# MDL_CONTROL.net
KiCad netlist of a schematic drawn in Altium Designer
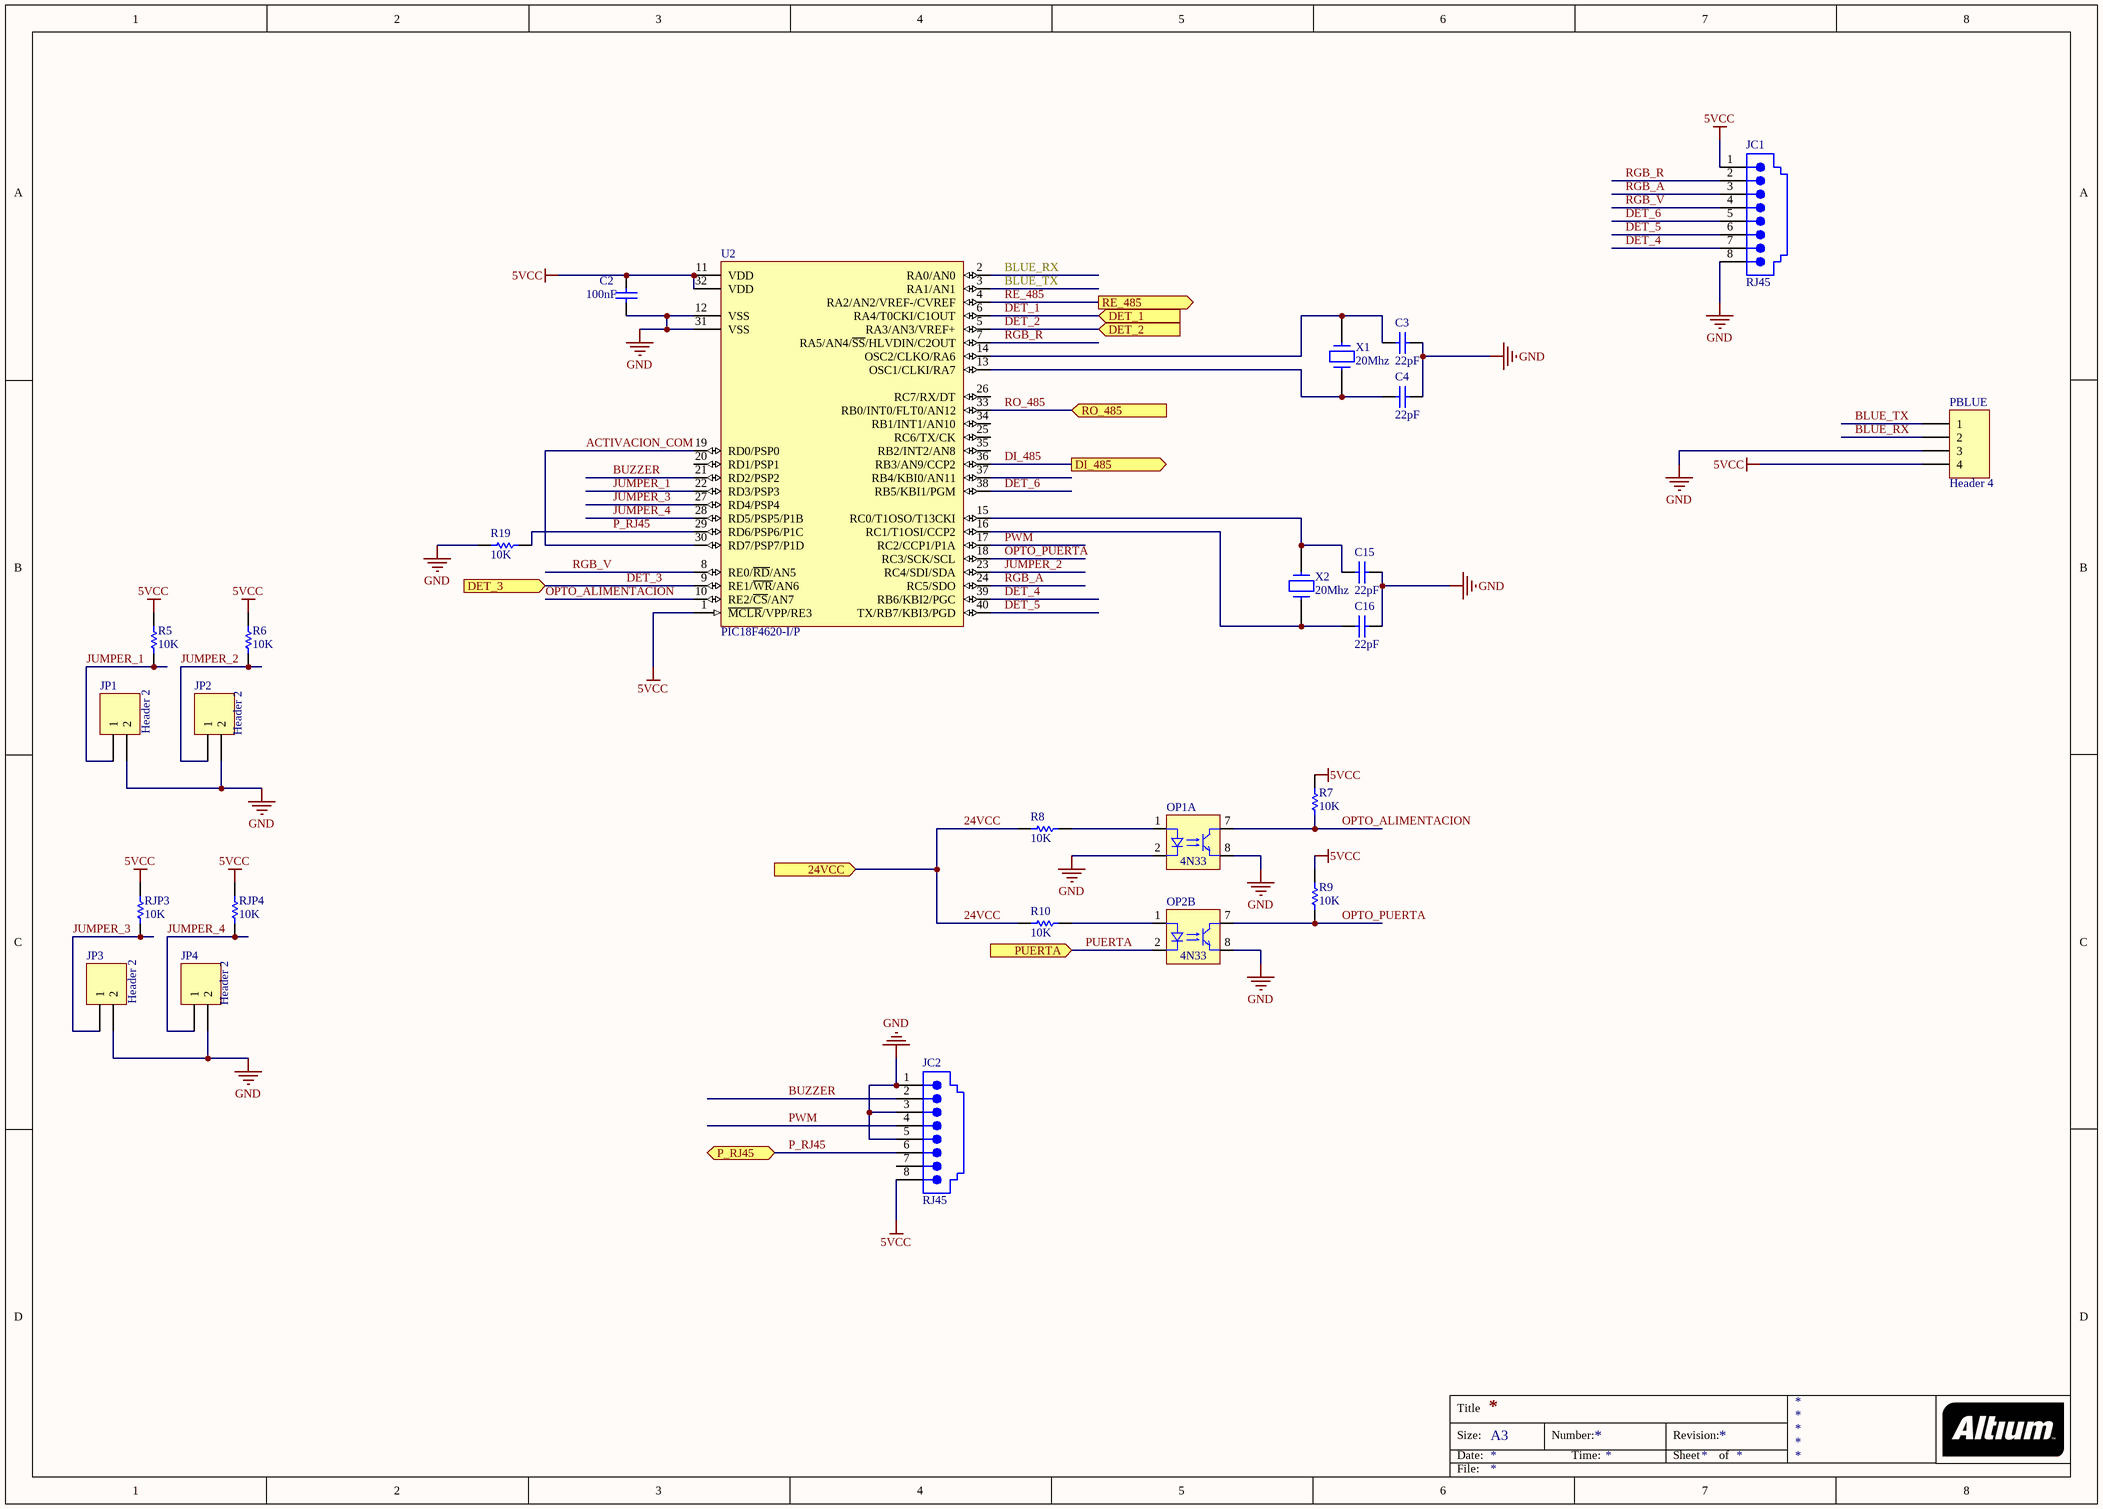
[diagram p0: MDL_CONTROL.SchDoc]

(export (version "E")
  (design (tool "Eeschema 10.0.6"))
  (components
    (comp (ref "C2")
      (value "100nF")
      (footprint "VP44-2.5")
      (description "Dipped Radial Multilayer Ceramic Capacitor X7R: 220nF, 100V")
      (fields (field (name "Comment") "VP44BY224JB") (field (name "PUBLISHER") "Altium Limited"))
      (libsource (lib "Vishay Vitramon Ceramic Dipped Capacitor") (part "VP44BY224JB"))
    )
    (comp (ref "C3")
      (value "22pF")
      (footprint "VP31-2.5")
      (description "Dipped Radial Multilayer Ceramic Capacitor COG (NPO): 22pF, 100V")
      (fields (field (name "Comment") "VP31BA220JB") (field (name "PUBLISHER") "Altium Limited"))
      (libsource (lib "Vishay Vitramon Ceramic Dipped Capacitor") (part "VP31BA220JB"))
    )
    (comp (ref "C4")
      (value "22pF")
      (footprint "VP31-2.5")
      (description "Dipped Radial Multilayer Ceramic Capacitor COG (NPO): 22pF, 100V")
      (fields (field (name "Comment") "VP31BA220JB") (field (name "PUBLISHER") "Altium Limited"))
      (libsource (lib "Vishay Vitramon Ceramic Dipped Capacitor") (part "VP31BA220JB"))
    )
    (comp (ref "C15")
      (value "22pF")
      (footprint "VP31-2.5")
      (description "Dipped Radial Multilayer Ceramic Capacitor COG (NPO): 22pF, 100V")
      (fields (field (name "Comment") "VP31BA220JB") (field (name "PUBLISHER") "Altium Limited"))
      (libsource (lib "Vishay Vitramon Ceramic Dipped Capacitor") (part "VP31BA220JB"))
    )
    (comp (ref "C16")
      (value "22pF")
      (footprint "VP31-2.5")
      (description "Dipped Radial Multilayer Ceramic Capacitor COG (NPO): 22pF, 100V")
      (fields (field (name "Comment") "VP31BA220JB") (field (name "PUBLISHER") "Altium Limited"))
      (libsource (lib "Vishay Vitramon Ceramic Dipped Capacitor") (part "VP31BA220JB"))
    )
    (comp (ref "JC1")
      (value "RJ45")
      (footprint "15-43-6233")
      (description "Right Angle, Standard Profile, RJ45-Keyed, Flange Mount PCB Jack")
      (fields (field (name "PUBLISHER") "Altium Limited"))
      (libsource (lib "Molex Modular Jack Right Angle") (part "15-43-6233"))
    )
    (comp (ref "JC2")
      (value "RJ45")
      (footprint "15-43-6233")
      (description "Right Angle, Standard Profile, RJ45-Keyed, Flange Mount PCB Jack")
      (fields (field (name "PUBLISHER") "Altium Limited"))
      (libsource (lib "Molex Modular Jack Right Angle") (part "15-43-6233"))
    )
    (comp (ref "JP1")
      (value "Header 2")
      (footprint "HDR1X2")
      (description "Header, 2-Pin")
      (fields (field (name "PUBLISHER") "Altium Limited"))
      (libsource (lib "Miscellaneous Connectors") (part "Header 2"))
    )
    (comp (ref "JP2")
      (value "Header 2")
      (footprint "HDR1X2")
      (description "Header, 2-Pin")
      (fields (field (name "PUBLISHER") "Altium Limited"))
      (libsource (lib "Miscellaneous Connectors") (part "Header 2"))
    )
    (comp (ref "JP3")
      (value "Header 2")
      (footprint "HDR1X2")
      (description "Header, 2-Pin")
      (fields (field (name "PUBLISHER") "Altium Limited"))
      (libsource (lib "Miscellaneous Connectors") (part "Header 2"))
    )
    (comp (ref "JP4")
      (value "Header 2")
      (footprint "HDR1X2")
      (description "Header, 2-Pin")
      (fields (field (name "PUBLISHER") "Altium Limited"))
      (libsource (lib "Miscellaneous Connectors") (part "Header 2"))
    )
    (comp (ref "OP1")
      (value "4N33")
      (footprint "4n35_4n33_6pines")
      (description "Optocoupler, Phototransistor Output, Dual Channel, TTL Compatible, Pb-free")
      (fields (field (name "PUBLISHER") "Altium Limited"))
      (libsource (lib "Vishay Optoelectronic Optocoupler") (part "ILD74"))
    )
    (comp (ref "OP2")
      (value "4N33")
      (footprint "4n35_4n33_6pines")
      (description "Optocoupler, Phototransistor Output, Dual Channel, TTL Compatible, Pb-free")
      (fields (field (name "PUBLISHER") "Altium Limited"))
      (libsource (lib "") (part "ILD74_1"))
    )
    (comp (ref "PBLUE")
      (value "Header 4")
      (footprint "HDR1X4")
      (description "Header, 4-Pin")
      (fields (field (name "PUBLISHER") "Altium Limited"))
      (libsource (lib "Miscellaneous Connectors") (part "Header 4"))
    )
    (comp (ref "R5")
      (value "10K")
      (footprint "AXIAL-0.3")
      (description "Resistor")
      (fields (field (name "Comment") "Res") (field (name "PUBLISHER") "Altium Limited"))
      (libsource (lib "Miscellaneous Devices") (part "Res1"))
    )
    (comp (ref "R6")
      (value "10K")
      (footprint "AXIAL-0.3")
      (description "Resistor")
      (fields (field (name "Comment") "Res") (field (name "PUBLISHER") "Altium Limited"))
      (libsource (lib "Miscellaneous Devices") (part "Res1"))
    )
    (comp (ref "R7")
      (value "10K")
      (footprint "AXIAL-0.3")
      (description "Resistor")
      (fields (field (name "Comment") "Res") (field (name "PUBLISHER") "Altium Limited"))
      (libsource (lib "Miscellaneous Devices") (part "Res1"))
    )
    (comp (ref "R8")
      (value "10K")
      (footprint "AXIAL-0.3")
      (description "Resistor")
      (fields (field (name "Comment") "Res") (field (name "PUBLISHER") "Altium Limited"))
      (libsource (lib "Miscellaneous Devices") (part "Res1"))
    )
    (comp (ref "R9")
      (value "10K")
      (footprint "AXIAL-0.3")
      (description "Resistor")
      (fields (field (name "Comment") "Res") (field (name "PUBLISHER") "Altium Limited"))
      (libsource (lib "Miscellaneous Devices") (part "Res1"))
    )
    (comp (ref "R10")
      (value "10K")
      (footprint "AXIAL-0.3")
      (description "Resistor")
      (fields (field (name "Comment") "Res") (field (name "PUBLISHER") "Altium Limited"))
      (libsource (lib "Miscellaneous Devices") (part "Res1"))
    )
    (comp (ref "R19")
      (value "10K")
      (footprint "AXIAL-0.3")
      (description "Resistor")
      (fields (field (name "Comment") "Res") (field (name "PUBLISHER") "Altium Limited"))
      (libsource (lib "Miscellaneous Devices") (part "Res1"))
    )
    (comp (ref "RJP3")
      (value "10K")
      (footprint "AXIAL-0.3")
      (description "Resistor")
      (fields (field (name "Comment") "Res") (field (name "PUBLISHER") "Altium Limited"))
      (libsource (lib "Miscellaneous Devices") (part "Res1"))
    )
    (comp (ref "RJP4")
      (value "10K")
      (footprint "AXIAL-0.3")
      (description "Resistor")
      (fields (field (name "Comment") "Res") (field (name "PUBLISHER") "Altium Limited"))
      (libsource (lib "Miscellaneous Devices") (part "Res1"))
    )
    (comp (ref "U2")
      (value "PIC18F4620-I/P")
      (footprint "PDIP600-P40")
      (fields (field (name "PUBLISHER") "Altium Limited"))
      (libsource (lib "Microchip Microcontroller 8-Bit PIC18") (part "PIC18F4620-I/P"))
    )
    (comp (ref "X1")
      (value "20Mhz")
      (footprint "XTAL-1")
      (description "Cristal de cuarzo")
      (fields (field (name "X1") "20Mhz"))
      (libsource (lib "Cristales de cuarzo") (part "Cristal de cuarzo"))
    )
    (comp (ref "X2")
      (value "20Mhz")
      (footprint "XTAL-1")
      (description "Cristal de cuarzo")
      (fields (field (name "X1") "20Mhz"))
      (libsource (lib "Cristales de cuarzo") (part "Cristal de cuarzo"))
    )
  )
  (nets
    (net (code "1") (name "/24VCC") (class "Default")
      (node (ref "R10") (pin "1") (pinfunction "1_1") (pintype "passive"))
      (node (ref "R8") (pin "1") (pinfunction "1_1") (pintype "passive"))
    )
    (net (code "2") (name "/ACTIVACION_COM") (class "Default")
      (node (ref "U2") (pin "19") (pinfunction "RD0/PSP0_19") (pintype "bidirectional"))
      (node (ref "U2") (pin "30") (pinfunction "RD7/PSP7/P1D_30") (pintype "bidirectional"))
    )
    (net (code "3") (name "/BLUE_RX") (class "Default")
      (node (ref "PBLUE") (pin "2") (pinfunction "2_2") (pintype "passive"))
      (node (ref "U2") (pin "2") (pinfunction "RA0/AN0_2") (pintype "bidirectional"))
    )
    (net (code "4") (name "/BLUE_TX") (class "Default")
      (node (ref "PBLUE") (pin "1") (pinfunction "1_1") (pintype "passive"))
      (node (ref "U2") (pin "3") (pinfunction "RA1/AN1_3") (pintype "bidirectional"))
    )
    (net (code "5") (name "/BUZZER") (class "Default")
      (node (ref "JC2") (pin "2") (pinfunction "2_2") (pintype "passive"))
      (node (ref "U2") (pin "21") (pinfunction "RD2/PSP2_21") (pintype "bidirectional"))
    )
    (net (code "6") (name "/DET_1") (class "Default")
      (node (ref "U2") (pin "6") (pinfunction "RA4/T0CKI/C1OUT_6") (pintype "bidirectional"))
    )
    (net (code "7") (name "/DET_2") (class "Default")
      (node (ref "U2") (pin "5") (pinfunction "RA3/AN3/VREF+_5") (pintype "bidirectional"))
    )
    (net (code "8") (name "/DET_3") (class "Default")
      (node (ref "U2") (pin "9") (pinfunction "RE1/~{WR}/AN6_9") (pintype "bidirectional"))
    )
    (net (code "9") (name "/DET_4") (class "Default")
      (node (ref "JC1") (pin "7") (pinfunction "7_7") (pintype "passive"))
      (node (ref "U2") (pin "39") (pinfunction "RB6/KBI2/PGC_39") (pintype "bidirectional"))
    )
    (net (code "10") (name "/DET_5") (class "Default")
      (node (ref "JC1") (pin "6") (pinfunction "6_6") (pintype "passive"))
      (node (ref "U2") (pin "40") (pinfunction "TX/RB7/KBI3/PGD_40") (pintype "bidirectional"))
    )
    (net (code "11") (name "/DET_6") (class "Default")
      (node (ref "JC1") (pin "5") (pinfunction "5_5") (pintype "passive"))
      (node (ref "U2") (pin "38") (pinfunction "RB5/KBI1/PGM_38") (pintype "bidirectional"))
    )
    (net (code "12") (name "/DI_485") (class "Default")
      (node (ref "U2") (pin "36") (pinfunction "RB3/AN9/CCP2_36") (pintype "bidirectional"))
    )
    (net (code "13") (name "/JUMPER_1") (class "Default")
      (node (ref "JP1") (pin "1") (pinfunction "1_1") (pintype "passive"))
      (node (ref "R5") (pin "1") (pinfunction "1_1") (pintype "passive"))
      (node (ref "U2") (pin "22") (pinfunction "RD3/PSP3_22") (pintype "bidirectional"))
    )
    (net (code "14") (name "/JUMPER_2") (class "Default")
      (node (ref "JP2") (pin "1") (pinfunction "1_1") (pintype "passive"))
      (node (ref "R6") (pin "1") (pinfunction "1_1") (pintype "passive"))
      (node (ref "U2") (pin "23") (pinfunction "RC4/SDI/SDA_23") (pintype "bidirectional"))
    )
    (net (code "15") (name "/JUMPER_3") (class "Default")
      (node (ref "JP3") (pin "1") (pinfunction "1_1") (pintype "passive"))
      (node (ref "RJP3") (pin "1") (pinfunction "1_1") (pintype "passive"))
      (node (ref "U2") (pin "27") (pinfunction "RD4/PSP4_27") (pintype "bidirectional"))
    )
    (net (code "16") (name "/JUMPER_4") (class "Default")
      (node (ref "JP4") (pin "1") (pinfunction "1_1") (pintype "passive"))
      (node (ref "RJP4") (pin "1") (pinfunction "1_1") (pintype "passive"))
      (node (ref "U2") (pin "28") (pinfunction "RD5/PSP5/P1B_28") (pintype "bidirectional"))
    )
    (net (code "17") (name "/OPTO_ALIMENTACION") (class "Default")
      (node (ref "OP1") (pin "7") (pinfunction "C_7") (pintype "passive"))
      (node (ref "R7") (pin "1") (pinfunction "1_1") (pintype "passive"))
      (node (ref "U2") (pin "10") (pinfunction "RE2/~{CS}/AN7_10") (pintype "bidirectional"))
    )
    (net (code "18") (name "/OPTO_PUERTA") (class "Default")
      (node (ref "OP2") (pin "7") (pinfunction "C_7") (pintype "passive"))
      (node (ref "R9") (pin "1") (pinfunction "1_1") (pintype "passive"))
      (node (ref "U2") (pin "18") (pinfunction "RC3/SCK/SCL_18") (pintype "bidirectional"))
    )
    (net (code "19") (name "/PUERTA") (class "Default")
      (node (ref "OP2") (pin "2") (pinfunction "K_2") (pintype "passive"))
    )
    (net (code "20") (name "/PWM") (class "Default")
      (node (ref "JC2") (pin "4") (pinfunction "4_4") (pintype "passive"))
      (node (ref "U2") (pin "17") (pinfunction "RC2/CCP1/P1A_17") (pintype "bidirectional"))
    )
    (net (code "21") (name "/P_RJ45") (class "Default")
      (node (ref "JC2") (pin "6") (pinfunction "6_6") (pintype "passive"))
      (node (ref "R19") (pin "1") (pinfunction "1_1") (pintype "passive"))
      (node (ref "U2") (pin "29") (pinfunction "RD6/PSP6/P1C_29") (pintype "bidirectional"))
    )
    (net (code "22") (name "/RE_485") (class "Default")
      (node (ref "U2") (pin "4") (pinfunction "RA2/AN2/VREF-/CVREF_4") (pintype "bidirectional"))
    )
    (net (code "23") (name "/RGB_A") (class "Default")
      (node (ref "JC1") (pin "3") (pinfunction "3_3") (pintype "passive"))
      (node (ref "U2") (pin "24") (pinfunction "RC5/SDO_24") (pintype "bidirectional"))
    )
    (net (code "24") (name "/RGB_R") (class "Default")
      (node (ref "JC1") (pin "2") (pinfunction "2_2") (pintype "passive"))
      (node (ref "U2") (pin "7") (pinfunction "RA5/AN4/~{SS}/HLVDIN/C2OUT_7") (pintype "bidirectional"))
    )
    (net (code "25") (name "/RGB_V") (class "Default")
      (node (ref "JC1") (pin "4") (pinfunction "4_4") (pintype "passive"))
      (node (ref "U2") (pin "8") (pinfunction "RE0/~{RD}/AN5_8") (pintype "bidirectional"))
    )
    (net (code "26") (name "/RO_485") (class "Default")
      (node (ref "U2") (pin "33") (pinfunction "RB0/INT0/FLT0/AN12_33") (pintype "bidirectional"))
    )
    (net (code "27") (name "5VCC") (class "Default")
      (node (ref "C2") (pin "1") (pinfunction "1_1") (pintype "passive"))
      (node (ref "JC1") (pin "1") (pinfunction "1_1") (pintype "passive"))
      (node (ref "JC2") (pin "8") (pinfunction "8_8") (pintype "passive"))
      (node (ref "PBLUE") (pin "4") (pinfunction "4_4") (pintype "passive"))
      (node (ref "R5") (pin "2") (pinfunction "2_2") (pintype "passive"))
      (node (ref "R6") (pin "2") (pinfunction "2_2") (pintype "passive"))
      (node (ref "R7") (pin "2") (pinfunction "2_2") (pintype "passive"))
      (node (ref "R9") (pin "2") (pinfunction "2_2") (pintype "passive"))
      (node (ref "RJP3") (pin "2") (pinfunction "2_2") (pintype "passive"))
      (node (ref "RJP4") (pin "2") (pinfunction "2_2") (pintype "passive"))
      (node (ref "U2") (pin "1") (pinfunction "~{MCLR}/VPP/RE3_1") (pintype "input"))
      (node (ref "U2") (pin "11") (pinfunction "VDD_11") (pintype "power_in"))
      (node (ref "U2") (pin "32") (pinfunction "VDD_32") (pintype "power_in"))
    )
    (net (code "28") (name "GND") (class "Default")
      (node (ref "C15") (pin "2") (pinfunction "2_2") (pintype "passive"))
      (node (ref "C16") (pin "1") (pinfunction "1_1") (pintype "passive"))
      (node (ref "C2") (pin "2") (pinfunction "2_2") (pintype "passive"))
      (node (ref "C3") (pin "2") (pinfunction "2_2") (pintype "passive"))
      (node (ref "C4") (pin "1") (pinfunction "1_1") (pintype "passive"))
      (node (ref "JC1") (pin "8") (pinfunction "8_8") (pintype "passive"))
      (node (ref "JC2") (pin "1") (pinfunction "1_1") (pintype "passive"))
      (node (ref "JC2") (pin "3") (pinfunction "3_3") (pintype "passive"))
      (node (ref "JC2") (pin "5") (pinfunction "5_5") (pintype "passive"))
      (node (ref "JP1") (pin "2") (pinfunction "2_2") (pintype "passive"))
      (node (ref "JP2") (pin "2") (pinfunction "2_2") (pintype "passive"))
      (node (ref "JP3") (pin "2") (pinfunction "2_2") (pintype "passive"))
      (node (ref "JP4") (pin "2") (pinfunction "2_2") (pintype "passive"))
      (node (ref "OP1") (pin "2") (pinfunction "K_2") (pintype "passive"))
      (node (ref "OP1") (pin "8") (pinfunction "E_8") (pintype "passive"))
      (node (ref "OP2") (pin "8") (pinfunction "E_8") (pintype "passive"))
      (node (ref "PBLUE") (pin "3") (pinfunction "3_3") (pintype "passive"))
      (node (ref "R19") (pin "2") (pinfunction "2_2") (pintype "passive"))
      (node (ref "U2") (pin "12") (pinfunction "VSS_12") (pintype "power_in"))
      (node (ref "U2") (pin "31") (pinfunction "VSS_31") (pintype "power_in"))
    )
    (net (code "29") (name "Net-(OP1A-A)") (class "Default")
      (node (ref "OP1") (pin "1") (pinfunction "A_1") (pintype "passive"))
      (node (ref "R8") (pin "2") (pinfunction "2_2") (pintype "passive"))
    )
    (net (code "30") (name "Net-(OP2B-A)") (class "Default")
      (node (ref "OP2") (pin "1") (pinfunction "A_1") (pintype "passive"))
      (node (ref "R10") (pin "2") (pinfunction "2_2") (pintype "passive"))
    )
    (net (code "31") (name "Net-(U2-OSC1{slash}CLKI{slash}RA7)") (class "Default")
      (node (ref "C4") (pin "2") (pinfunction "2_2") (pintype "passive"))
      (node (ref "U2") (pin "13") (pinfunction "OSC1/CLKI/RA7_13") (pintype "bidirectional"))
      (node (ref "X1") (pin "2") (pinfunction "2_2") (pintype "passive"))
    )
    (net (code "32") (name "Net-(U2-OSC2{slash}CLKO{slash}RA6)") (class "Default")
      (node (ref "C3") (pin "1") (pinfunction "1_1") (pintype "passive"))
      (node (ref "U2") (pin "14") (pinfunction "OSC2/CLKO/RA6_14") (pintype "bidirectional"))
      (node (ref "X1") (pin "1") (pinfunction "1_1") (pintype "passive"))
    )
    (net (code "33") (name "Net-(U2-RC0{slash}T1OSO{slash}T13CKI)") (class "Default")
      (node (ref "C15") (pin "1") (pinfunction "1_1") (pintype "passive"))
      (node (ref "U2") (pin "15") (pinfunction "RC0/T1OSO/T13CKI_15") (pintype "bidirectional"))
      (node (ref "X2") (pin "1") (pinfunction "1_1") (pintype "passive"))
    )
    (net (code "34") (name "Net-(U2-RC1{slash}T1OSI{slash}CCP2)") (class "Default")
      (node (ref "C16") (pin "2") (pinfunction "2_2") (pintype "passive"))
      (node (ref "U2") (pin "16") (pinfunction "RC1/T1OSI/CCP2_16") (pintype "bidirectional"))
      (node (ref "X2") (pin "2") (pinfunction "2_2") (pintype "passive"))
    )
    (net (code "35") (name "unconnected-(JC2-Pad7)") (class "Default")
      (node (ref "JC2") (pin "7") (pinfunction "7_7") (pintype "passive"))
    )
    (net (code "36") (name "unconnected-(U2-RB1{slash}INT1{slash}AN10-Pad34)") (class "Default")
      (node (ref "U2") (pin "34") (pinfunction "RB1/INT1/AN10_34") (pintype "bidirectional"))
    )
    (net (code "37") (name "unconnected-(U2-RB2{slash}INT2{slash}AN8-Pad35)") (class "Default")
      (node (ref "U2") (pin "35") (pinfunction "RB2/INT2/AN8_35") (pintype "bidirectional"))
    )
    (net (code "38") (name "unconnected-(U2-RB4{slash}KBI0{slash}AN11-Pad37)") (class "Default")
      (node (ref "U2") (pin "37") (pinfunction "RB4/KBI0/AN11_37") (pintype "bidirectional"))
    )
    (net (code "39") (name "unconnected-(U2-RC6{slash}TX{slash}CK-Pad25)") (class "Default")
      (node (ref "U2") (pin "25") (pinfunction "RC6/TX/CK_25") (pintype "bidirectional"))
    )
    (net (code "40") (name "unconnected-(U2-RC7{slash}RX{slash}DT-Pad26)") (class "Default")
      (node (ref "U2") (pin "26") (pinfunction "RC7/RX/DT_26") (pintype "bidirectional"))
    )
    (net (code "41") (name "unconnected-(U2-RD1{slash}PSP1-Pad20)") (class "Default")
      (node (ref "U2") (pin "20") (pinfunction "RD1/PSP1_20") (pintype "bidirectional"))
    )
  )
)
